# cdz7shld1.net
KiCad netlist of a schematic drawn in EAGLE
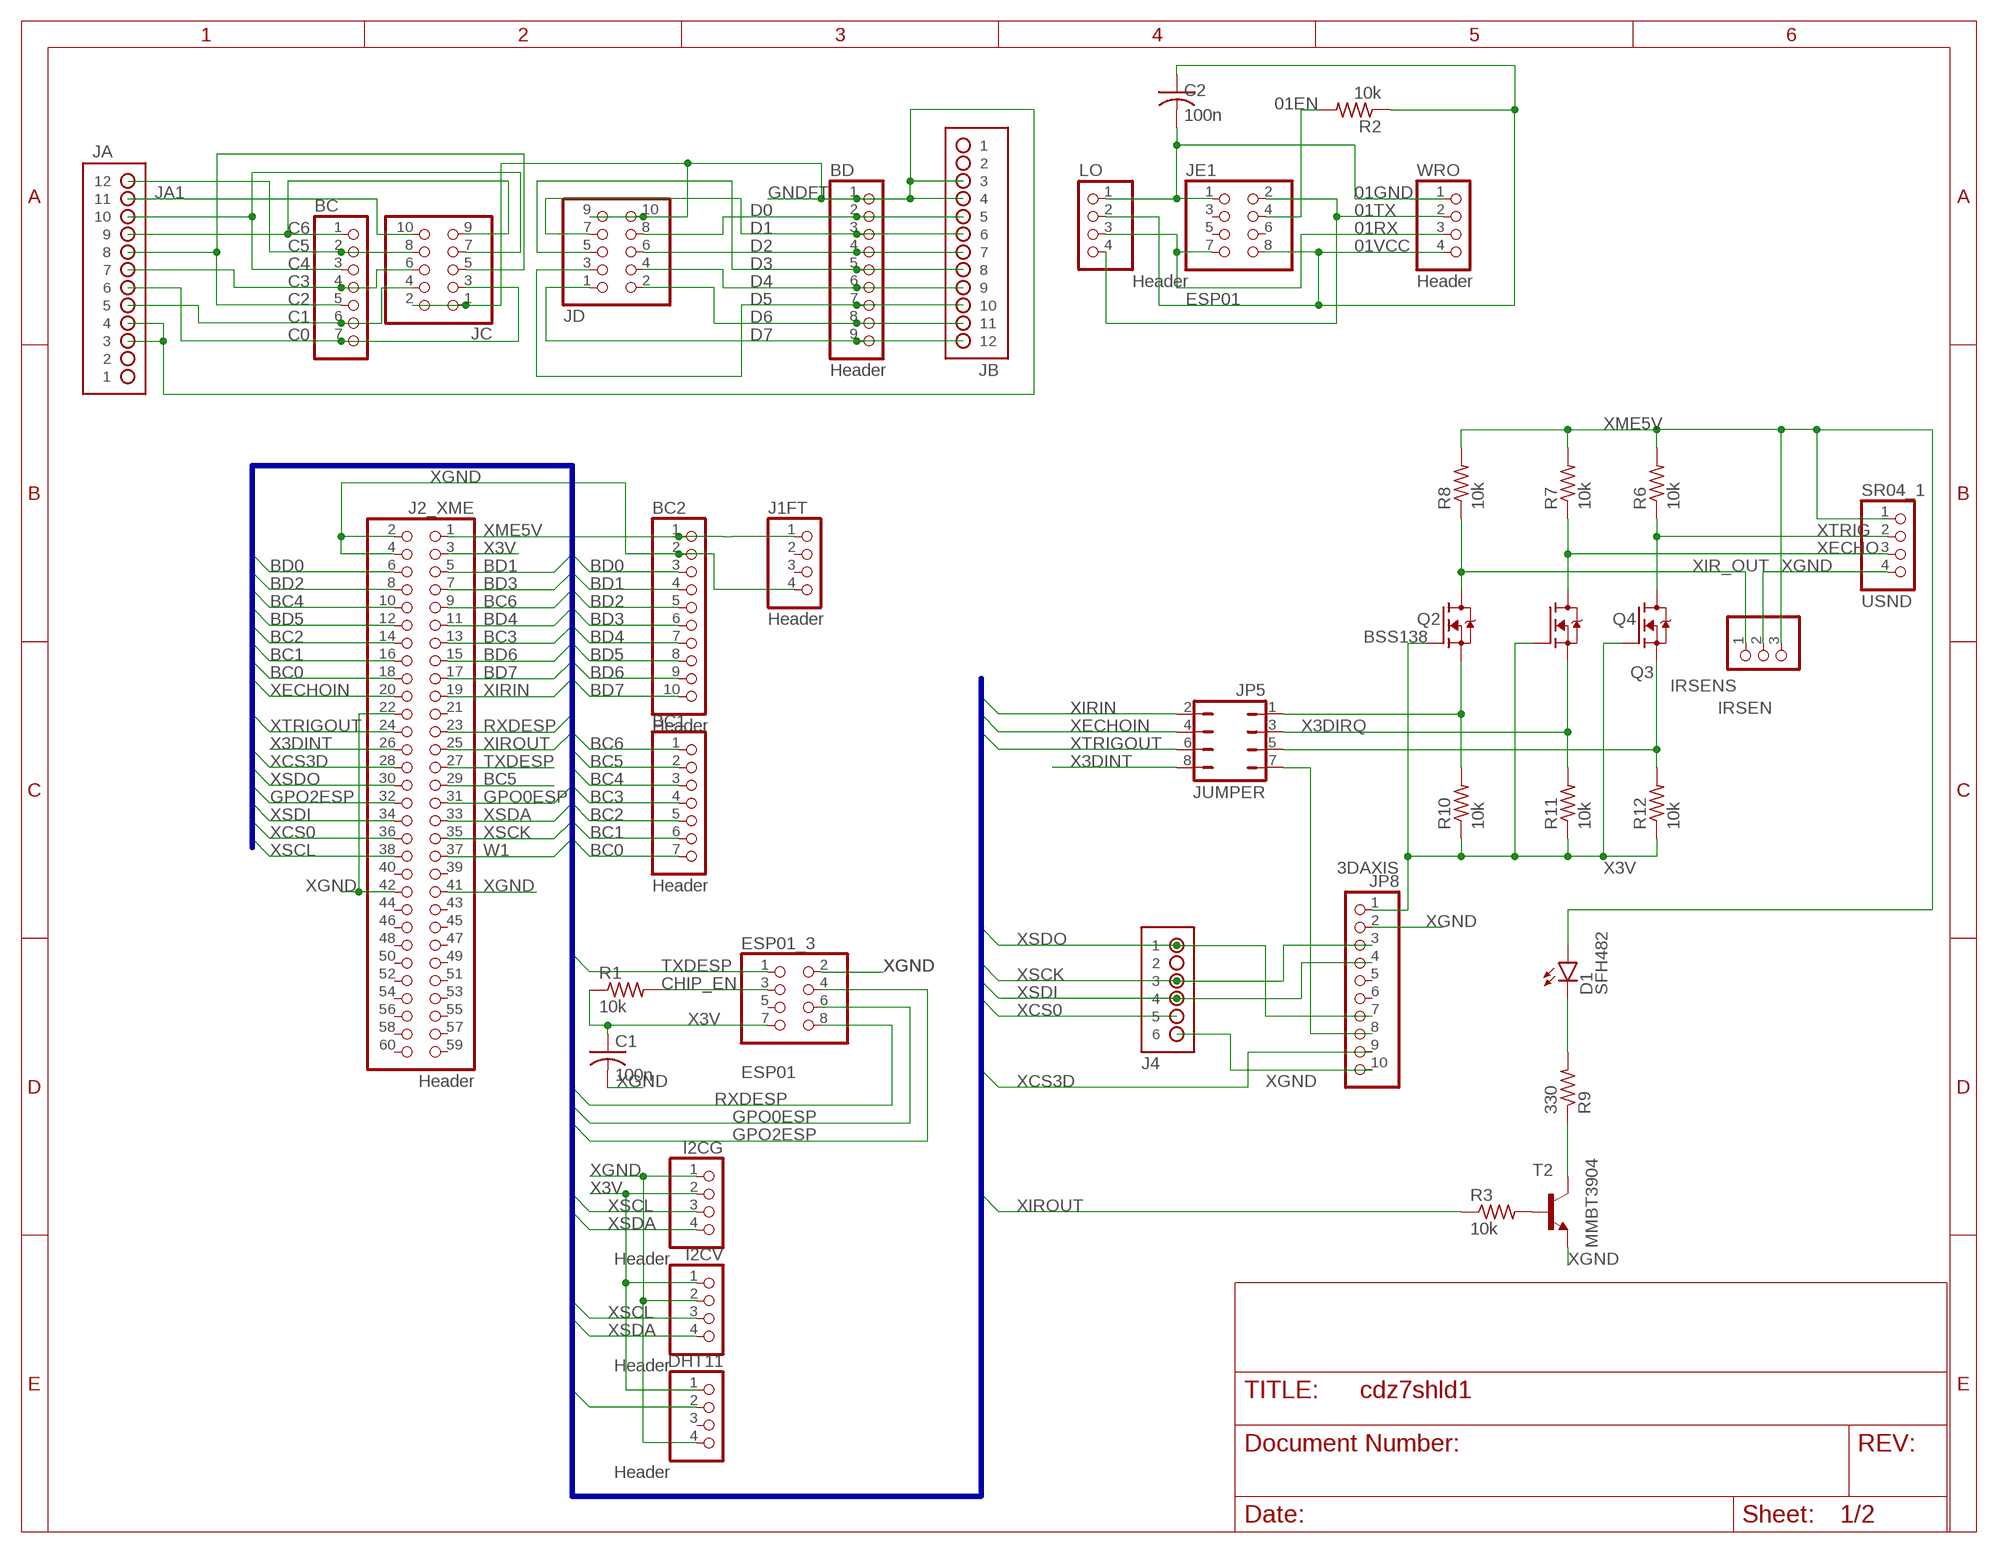
[diagram p0: schematic, sheet 1]
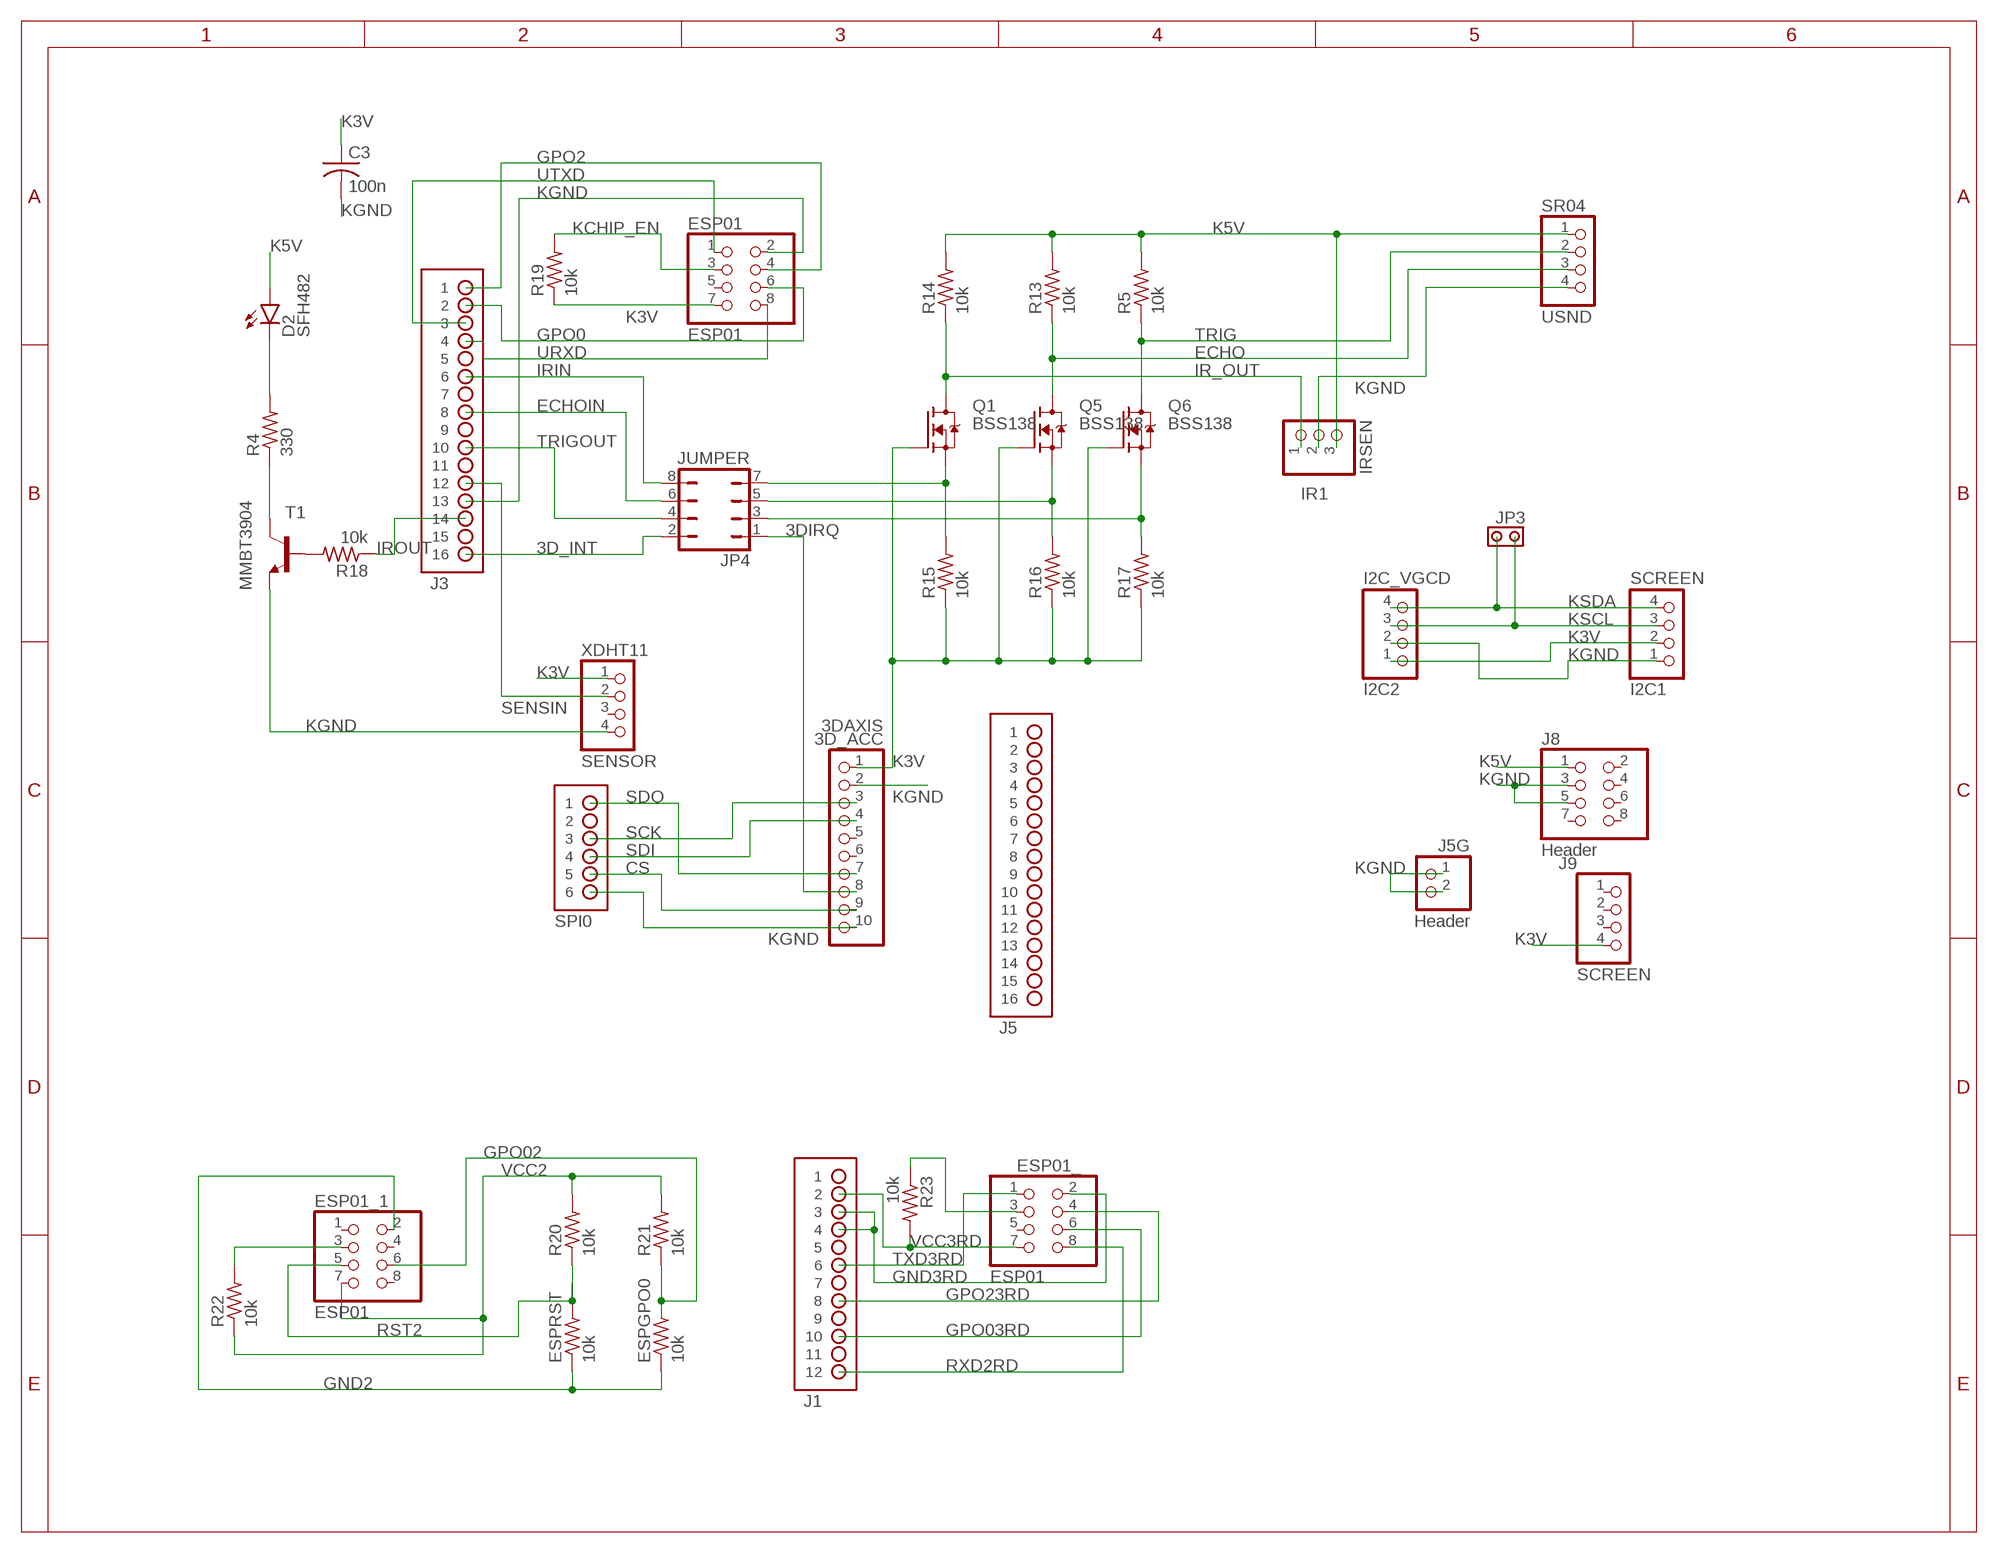
[diagram p1: schematic, sheet 2]

(export (version "E")
  (design (tool "Eeschema 10.0.6"))
  (components
    (comp (ref "3D_ACC")
      (value "3DAXIS")
      (footprint "eagle-import:1X10")
      (libsource (lib "eagle-import") (part "PINHD-1X10"))
    )
    (comp (ref "C3")
      (value "100n")
      (footprint "eagle-import:C0402")
      (libsource (lib "eagle-import") (part "C-USC0402"))
    )
    (comp (ref "D2")
      (value "SFH482")
      (footprint "eagle-import:SFH482")
      (libsource (lib "eagle-import") (part "SFH482"))
    )
    (comp (ref "ESP01")
      (value "ESP01")
      (footprint "eagle-import:2X04")
      (libsource (lib "eagle-import") (part "pinhead_325_PINHD-2X4"))
    )
    (comp (ref "ESP01_")
      (value "ESP01")
      (footprint "eagle-import:2X04")
      (libsource (lib "eagle-import") (part "pinhead_325_PINHD-2X4"))
    )
    (comp (ref "ESP01_1")
      (value "ESP01")
      (footprint "eagle-import:2X04")
      (libsource (lib "eagle-import") (part "pinhead_325_PINHD-2X4"))
    )
    (comp (ref "ESPGPO0")
      (value "10k")
      (footprint "eagle-import:0204_5")
      (libsource (lib "eagle-import") (part "R-US_0204/5"))
    )
    (comp (ref "ESPRST")
      (value "10k")
      (footprint "eagle-import:0204_5")
      (libsource (lib "eagle-import") (part "R-US_0204/5"))
    )
    (comp (ref "I2C1")
      (value "SCREEN")
      (footprint "eagle-import:1X04")
      (libsource (lib "eagle-import") (part "PINHD-1X4"))
    )
    (comp (ref "I2C2")
      (value "I2C_VGCD")
      (footprint "eagle-import:1X04")
      (libsource (lib "eagle-import") (part "PINHD-1X4"))
    )
    (comp (ref "IR1")
      (value "IRSEN")
      (footprint "eagle-import:1X03")
      (libsource (lib "eagle-import") (part "PINHD-1X3"))
    )
    (comp (ref "J1")
      (value "HDR-2X6")
      (footprint "eagle-import:HDR-2X6")
      (libsource (lib "eagle-import") (part "HDR-2X6"))
    )
    (comp (ref "J3")
      (value "HDR-2X8")
      (footprint "eagle-import:HDR-2X8")
      (libsource (lib "eagle-import") (part "HDR-2X8"))
    )
    (comp (ref "J5")
      (value "HDR-2X8")
      (footprint "eagle-import:HDR-2X8")
      (libsource (lib "eagle-import") (part "HDR-2X8"))
    )
    (comp (ref "J5G")
      (value "Header")
      (footprint "eagle-import:1X02")
      (libsource (lib "eagle-import") (part "PINHD-1X2"))
    )
    (comp (ref "J8")
      (value "Header")
      (footprint "eagle-import:2X04")
      (libsource (lib "eagle-import") (part "PINHD-2X4"))
    )
    (comp (ref "J9")
      (value "SCREEN")
      (footprint "eagle-import:1X04")
      (libsource (lib "eagle-import") (part "PINHD-1X4"))
    )
    (comp (ref "JP3")
      (value "JPR-1X2")
      (footprint "eagle-import:JPR-1X2")
      (libsource (lib "eagle-import") (part "JPR-1X2"))
    )
    (comp (ref "JP4")
      (value "JUMPER")
      (footprint "eagle-import:JP4Q")
      (libsource (lib "eagle-import") (part "JP4Q"))
    )
    (comp (ref "Q1")
      (value "BSS138")
      (footprint "eagle-import:SOT23")
      (fields (field (name "MF") "Fairchild"))
      (libsource (lib "eagle-import") (part "BSS138"))
    )
    (comp (ref "Q5")
      (value "BSS138")
      (footprint "eagle-import:SOT23")
      (fields (field (name "MF") "Fairchild"))
      (libsource (lib "eagle-import") (part "BSS138"))
    )
    (comp (ref "Q6")
      (value "BSS138")
      (footprint "eagle-import:SOT23")
      (fields (field (name "MF") "Fairchild"))
      (libsource (lib "eagle-import") (part "BSS138"))
    )
    (comp (ref "R4")
      (value "330")
      (footprint "eagle-import:R0402")
      (libsource (lib "eagle-import") (part "R-US_R0402"))
    )
    (comp (ref "R5")
      (value "10k")
      (footprint "eagle-import:R0402")
      (libsource (lib "eagle-import") (part "R-US_R0402"))
    )
    (comp (ref "R13")
      (value "10k")
      (footprint "eagle-import:R0402")
      (libsource (lib "eagle-import") (part "R-US_R0402"))
    )
    (comp (ref "R14")
      (value "10k")
      (footprint "eagle-import:R0402")
      (libsource (lib "eagle-import") (part "R-US_R0402"))
    )
    (comp (ref "R15")
      (value "10k")
      (footprint "eagle-import:R0402")
      (libsource (lib "eagle-import") (part "R-US_R0402"))
    )
    (comp (ref "R16")
      (value "10k")
      (footprint "eagle-import:R0402")
      (libsource (lib "eagle-import") (part "R-US_R0402"))
    )
    (comp (ref "R17")
      (value "10k")
      (footprint "eagle-import:R0402")
      (libsource (lib "eagle-import") (part "R-US_R0402"))
    )
    (comp (ref "R18")
      (value "10k")
      (footprint "eagle-import:R0402")
      (libsource (lib "eagle-import") (part "R-US_R0402"))
    )
    (comp (ref "R19")
      (value "10k")
      (footprint "eagle-import:R0402")
      (libsource (lib "eagle-import") (part "R-US_R0402"))
    )
    (comp (ref "R20")
      (value "10k")
      (footprint "eagle-import:R0402")
      (libsource (lib "eagle-import") (part "R-US_R0402"))
    )
    (comp (ref "R21")
      (value "10k")
      (footprint "eagle-import:R0402")
      (libsource (lib "eagle-import") (part "R-US_R0402"))
    )
    (comp (ref "R22")
      (value "10k")
      (footprint "eagle-import:R0402")
      (libsource (lib "eagle-import") (part "R-US_R0402"))
    )
    (comp (ref "R23")
      (value "10k")
      (footprint "eagle-import:R0402")
      (libsource (lib "eagle-import") (part "R-US_R0402"))
    )
    (comp (ref "SPI0")
      (value "HDR-2X3")
      (footprint "eagle-import:HDR-2X3")
      (libsource (lib "eagle-import") (part "HDR-2X3"))
    )
    (comp (ref "SR04")
      (value "USND")
      (footprint "eagle-import:1X04")
      (libsource (lib "eagle-import") (part "PINHD-1X4"))
    )
    (comp (ref "T1")
      (value "MMBT3904")
      (footprint "eagle-import:SOT23-BEC")
      (libsource (lib "eagle-import") (part "-NPN-SOT23-BECMMBT3904LT1"))
    )
    (comp (ref "XDHT11")
      (value "SENSOR")
      (footprint "eagle-import:1X04")
      (libsource (lib "eagle-import") (part "PINHD-1X4"))
    )
    (comp (ref "BC")
      (value "Header")
      (footprint "eagle-import:1X07")
      (libsource (lib "eagle-import") (part "PINHD-1X7"))
    )
    (comp (ref "BC1")
      (value "Header")
      (footprint "eagle-import:1X07")
      (libsource (lib "eagle-import") (part "PINHD-1X7"))
    )
    (comp (ref "BC2")
      (value "Header")
      (footprint "eagle-import:1X10")
      (libsource (lib "eagle-import") (part "PINHD-1X10"))
    )
    (comp (ref "BD")
      (value "Header")
      (footprint "eagle-import:1X09")
      (libsource (lib "eagle-import") (part "PINHD-1X9"))
    )
    (comp (ref "C1")
      (value "100n")
      (footprint "eagle-import:C0402")
      (libsource (lib "eagle-import") (part "C-USC0402"))
    )
    (comp (ref "C2")
      (value "100n")
      (footprint "eagle-import:C0402")
      (libsource (lib "eagle-import") (part "C-USC0402"))
    )
    (comp (ref "D1")
      (value "SFH482")
      (footprint "eagle-import:SFH482")
      (libsource (lib "eagle-import") (part "SFH482"))
    )
    (comp (ref "DHT11")
      (value "Header")
      (footprint "eagle-import:1X04")
      (libsource (lib "eagle-import") (part "PINHD-1X4"))
    )
    (comp (ref "ESP01_3")
      (value "ESP01")
      (footprint "eagle-import:2X04")
      (libsource (lib "eagle-import") (part "pinhead_325_PINHD-2X4"))
    )
    (comp (ref "I2CG")
      (value "Header")
      (footprint "eagle-import:1X04")
      (libsource (lib "eagle-import") (part "PINHD-1X4"))
    )
    (comp (ref "I2CV")
      (value "Header")
      (footprint "eagle-import:1X04")
      (libsource (lib "eagle-import") (part "PINHD-1X4"))
    )
    (comp (ref "IRSENS")
      (value "IRSEN")
      (footprint "eagle-import:1X03")
      (libsource (lib "eagle-import") (part "PINHD-1X3"))
    )
    (comp (ref "J1FT")
      (value "Header")
      (footprint "eagle-import:1X04")
      (libsource (lib "eagle-import") (part "PINHD-1X4"))
    )
    (comp (ref "J2_XME")
      (value "Header")
      (footprint "eagle-import:2X30")
      (libsource (lib "eagle-import") (part "PINHD-2X30"))
    )
    (comp (ref "J4")
      (value "HDR-2X3")
      (footprint "eagle-import:HDR-2X3")
      (libsource (lib "eagle-import") (part "HDR-2X3"))
    )
    (comp (ref "JA")
      (value "HDR-2X6")
      (footprint "eagle-import:HDR-2X6")
      (libsource (lib "eagle-import") (part "HDR-2X6"))
    )
    (comp (ref "JB")
      (value "HDR-2X6")
      (footprint "eagle-import:HDR-2X6")
      (libsource (lib "eagle-import") (part "HDR-2X6"))
    )
    (comp (ref "JC")
      (value "Header")
      (footprint "eagle-import:2X05")
      (libsource (lib "eagle-import") (part "PINHD-2X5"))
    )
    (comp (ref "JD")
      (value "Header")
      (footprint "eagle-import:2X05")
      (libsource (lib "eagle-import") (part "PINHD-2X5"))
    )
    (comp (ref "JE1")
      (value "ESP01")
      (footprint "eagle-import:2X04")
      (libsource (lib "eagle-import") (part "pinhead_325_PINHD-2X4"))
    )
    (comp (ref "JP5")
      (value "JUMPER")
      (footprint "eagle-import:JP4Q")
      (libsource (lib "eagle-import") (part "JP4Q"))
    )
    (comp (ref "JP8")
      (value "3DAXIS")
      (footprint "eagle-import:1X10")
      (libsource (lib "eagle-import") (part "PINHD-1X10"))
    )
    (comp (ref "LO")
      (value "Header")
      (footprint "eagle-import:1X04")
      (libsource (lib "eagle-import") (part "PINHD-1X4"))
    )
    (comp (ref "Q2")
      (value "BSS138")
      (footprint "eagle-import:SOT23")
      (fields (field (name "MF") "Fairchild"))
      (libsource (lib "eagle-import") (part "BSS138"))
    )
    (comp (ref "Q3")
      (value "BSS138")
      (footprint "eagle-import:SOT23")
      (fields (field (name "MF") "Fairchild"))
      (libsource (lib "eagle-import") (part "BSS138"))
    )
    (comp (ref "Q4")
      (value "BSS138")
      (footprint "eagle-import:SOT23")
      (fields (field (name "MF") "Fairchild"))
      (libsource (lib "eagle-import") (part "BSS138"))
    )
    (comp (ref "R1")
      (value "10k")
      (footprint "eagle-import:R0402")
      (libsource (lib "eagle-import") (part "R-US_R0402"))
    )
    (comp (ref "R2")
      (value "10k")
      (footprint "eagle-import:R0402")
      (libsource (lib "eagle-import") (part "R-US_R0402"))
    )
    (comp (ref "R3")
      (value "10k")
      (footprint "eagle-import:R0402")
      (libsource (lib "eagle-import") (part "R-US_R0402"))
    )
    (comp (ref "R6")
      (value "10k")
      (footprint "eagle-import:R0402")
      (libsource (lib "eagle-import") (part "R-US_R0402"))
    )
    (comp (ref "R7")
      (value "10k")
      (footprint "eagle-import:R0402")
      (libsource (lib "eagle-import") (part "R-US_R0402"))
    )
    (comp (ref "R8")
      (value "10k")
      (footprint "eagle-import:R0402")
      (libsource (lib "eagle-import") (part "R-US_R0402"))
    )
    (comp (ref "R9")
      (value "330")
      (footprint "eagle-import:R0402")
      (libsource (lib "eagle-import") (part "R-US_R0402"))
    )
    (comp (ref "R10")
      (value "10k")
      (footprint "eagle-import:R0402")
      (libsource (lib "eagle-import") (part "R-US_R0402"))
    )
    (comp (ref "R11")
      (value "10k")
      (footprint "eagle-import:R0402")
      (libsource (lib "eagle-import") (part "R-US_R0402"))
    )
    (comp (ref "R12")
      (value "10k")
      (footprint "eagle-import:R0402")
      (libsource (lib "eagle-import") (part "R-US_R0402"))
    )
    (comp (ref "SR04_1")
      (value "USND")
      (footprint "eagle-import:1X04")
      (libsource (lib "eagle-import") (part "PINHD-1X4"))
    )
    (comp (ref "T2")
      (value "MMBT3904")
      (footprint "eagle-import:SOT23-BEC")
      (libsource (lib "eagle-import") (part "-NPN-SOT23-BECMMBT3904LT1"))
    )
    (comp (ref "WRO")
      (value "Header")
      (footprint "eagle-import:1X04")
      (libsource (lib "eagle-import") (part "PINHD-1X4"))
    )
  )
  (nets
    (net (code "1") (name "01EN") (class "Default")
      (node (ref "JE1") (pin "4") (pinfunction "4_4") (pintype "passive"))
      (node (ref "R2") (pin "2") (pinfunction "2_2") (pintype "passive"))
    )
    (net (code "2") (name "01GND") (class "Default")
      (node (ref "C2") (pin "2") (pinfunction "2_2") (pintype "passive"))
      (node (ref "JE1") (pin "1") (pinfunction "1_1") (pintype "passive"))
      (node (ref "LO") (pin "1") (pinfunction "1_1") (pintype "passive"))
      (node (ref "WRO") (pin "1") (pinfunction "1_1") (pintype "passive"))
    )
    (net (code "3") (name "01RX") (class "Default")
      (node (ref "JE1") (pin "7") (pinfunction "7_7") (pintype "passive"))
      (node (ref "LO") (pin "3") (pinfunction "3_3") (pintype "passive"))
      (node (ref "WRO") (pin "3") (pinfunction "3_3") (pintype "passive"))
    )
    (net (code "4") (name "01TX") (class "Default")
      (node (ref "JE1") (pin "2") (pinfunction "2_2") (pintype "passive"))
      (node (ref "LO") (pin "4") (pinfunction "4_4") (pintype "passive"))
      (node (ref "WRO") (pin "2") (pinfunction "2_2") (pintype "passive"))
    )
    (net (code "5") (name "01VCC") (class "Default")
      (node (ref "C2") (pin "1") (pinfunction "1_1") (pintype "passive"))
      (node (ref "JE1") (pin "8") (pinfunction "8_8") (pintype "passive"))
      (node (ref "LO") (pin "2") (pinfunction "2_2") (pintype "passive"))
      (node (ref "R2") (pin "1") (pinfunction "1_1") (pintype "passive"))
      (node (ref "WRO") (pin "4") (pinfunction "4_4") (pintype "passive"))
    )
    (net (code "6") (name "3DIRQ") (class "Default")
      (node (ref "3D_ACC") (pin "8") (pinfunction "8_8") (pintype "passive"))
      (node (ref "JP4") (pin "1") (pinfunction "1_1") (pintype "passive"))
    )
    (net (code "7") (name "3D_INT") (class "Default")
      (node (ref "J3") (pin "16") (pinfunction "16_16") (pintype "passive"))
      (node (ref "JP4") (pin "2") (pinfunction "2_2") (pintype "passive"))
    )
    (net (code "8") (name "BC0") (class "Default")
      (node (ref "BC1") (pin "7") (pinfunction "7_7") (pintype "passive"))
      (node (ref "J2_XME") (pin "18") (pinfunction "18_18") (pintype "passive"))
    )
    (net (code "9") (name "BC1") (class "Default")
      (node (ref "BC1") (pin "6") (pinfunction "6_6") (pintype "passive"))
      (node (ref "J2_XME") (pin "16") (pinfunction "16_16") (pintype "passive"))
    )
    (net (code "10") (name "BC2") (class "Default")
      (node (ref "BC1") (pin "5") (pinfunction "5_5") (pintype "passive"))
      (node (ref "J2_XME") (pin "14") (pinfunction "14_14") (pintype "passive"))
    )
    (net (code "11") (name "BC3") (class "Default")
      (node (ref "BC1") (pin "4") (pinfunction "4_4") (pintype "passive"))
      (node (ref "J2_XME") (pin "13") (pinfunction "13_13") (pintype "passive"))
    )
    (net (code "12") (name "BC4") (class "Default")
      (node (ref "BC1") (pin "3") (pinfunction "3_3") (pintype "passive"))
      (node (ref "J2_XME") (pin "10") (pinfunction "10_10") (pintype "passive"))
    )
    (net (code "13") (name "BC5") (class "Default")
      (node (ref "BC1") (pin "2") (pinfunction "2_2") (pintype "passive"))
      (node (ref "J2_XME") (pin "29") (pinfunction "29_29") (pintype "passive"))
    )
    (net (code "14") (name "BC6") (class "Default")
      (node (ref "BC1") (pin "1") (pinfunction "1_1") (pintype "passive"))
      (node (ref "J2_XME") (pin "9") (pinfunction "9_9") (pintype "passive"))
    )
    (net (code "15") (name "BD0") (class "Default")
      (node (ref "BC2") (pin "3") (pinfunction "3_3") (pintype "passive"))
      (node (ref "J2_XME") (pin "6") (pinfunction "6_6") (pintype "passive"))
    )
    (net (code "16") (name "BD1") (class "Default")
      (node (ref "BC2") (pin "4") (pinfunction "4_4") (pintype "passive"))
      (node (ref "J2_XME") (pin "5") (pinfunction "5_5") (pintype "passive"))
    )
    (net (code "17") (name "BD2") (class "Default")
      (node (ref "BC2") (pin "5") (pinfunction "5_5") (pintype "passive"))
      (node (ref "J2_XME") (pin "8") (pinfunction "8_8") (pintype "passive"))
    )
    (net (code "18") (name "BD3") (class "Default")
      (node (ref "BC2") (pin "6") (pinfunction "6_6") (pintype "passive"))
      (node (ref "J2_XME") (pin "7") (pinfunction "7_7") (pintype "passive"))
    )
    (net (code "19") (name "BD4") (class "Default")
      (node (ref "BC2") (pin "7") (pinfunction "7_7") (pintype "passive"))
      (node (ref "J2_XME") (pin "11") (pinfunction "11_11") (pintype "passive"))
    )
    (net (code "20") (name "BD5") (class "Default")
      (node (ref "BC2") (pin "8") (pinfunction "8_8") (pintype "passive"))
      (node (ref "J2_XME") (pin "12") (pinfunction "12_12") (pintype "passive"))
    )
    (net (code "21") (name "BD6") (class "Default")
      (node (ref "BC2") (pin "9") (pinfunction "9_9") (pintype "passive"))
      (node (ref "J2_XME") (pin "15") (pinfunction "15_15") (pintype "passive"))
    )
    (net (code "22") (name "BD7") (class "Default")
      (node (ref "BC2") (pin "10") (pinfunction "10_10") (pintype "passive"))
      (node (ref "J2_XME") (pin "17") (pinfunction "17_17") (pintype "passive"))
    )
    (net (code "23") (name "C0") (class "Default")
      (node (ref "BC") (pin "7") (pinfunction "7_7") (pintype "passive"))
      (node (ref "JA") (pin "6") (pinfunction "6_6") (pintype "passive"))
      (node (ref "JC") (pin "3") (pinfunction "3_3") (pintype "passive"))
    )
    (net (code "24") (name "C1") (class "Default")
      (node (ref "BC") (pin "6") (pinfunction "6_6") (pintype "passive"))
      (node (ref "JA") (pin "5") (pinfunction "5_5") (pintype "passive"))
      (node (ref "JC") (pin "4") (pinfunction "4_4") (pintype "passive"))
    )
    (net (code "25") (name "C2") (class "Default")
      (node (ref "BC") (pin "5") (pinfunction "5_5") (pintype "passive"))
      (node (ref "JA") (pin "8") (pinfunction "8_8") (pintype "passive"))
      (node (ref "JC") (pin "5") (pinfunction "5_5") (pintype "passive"))
    )
    (net (code "26") (name "C3") (class "Default")
      (node (ref "BC") (pin "4") (pinfunction "4_4") (pintype "passive"))
      (node (ref "JA") (pin "7") (pinfunction "7_7") (pintype "passive"))
      (node (ref "JC") (pin "6") (pinfunction "6_6") (pintype "passive"))
    )
    (net (code "27") (name "C4") (class "Default")
      (node (ref "BC") (pin "3") (pinfunction "3_3") (pintype "passive"))
      (node (ref "JA") (pin "10") (pinfunction "10_10") (pintype "passive"))
      (node (ref "JC") (pin "7") (pinfunction "7_7") (pintype "passive"))
    )
    (net (code "28") (name "C5") (class "Default")
      (node (ref "BC") (pin "2") (pinfunction "2_2") (pintype "passive"))
      (node (ref "JA") (pin "12") (pinfunction "12_12") (pintype "passive"))
      (node (ref "JC") (pin "8") (pinfunction "8_8") (pintype "passive"))
    )
    (net (code "29") (name "C6") (class "Default")
      (node (ref "BC") (pin "1") (pinfunction "1_1") (pintype "passive"))
      (node (ref "JA") (pin "9") (pinfunction "9_9") (pintype "passive"))
      (node (ref "JC") (pin "9") (pinfunction "9_9") (pintype "passive"))
    )
    (net (code "30") (name "CHIP_EN") (class "Default")
      (node (ref "ESP01_3") (pin "3") (pinfunction "3_3") (pintype "passive"))
      (node (ref "R1") (pin "2") (pinfunction "2_2") (pintype "passive"))
    )
    (net (code "31") (name "CS") (class "Default")
      (node (ref "3D_ACC") (pin "9") (pinfunction "9_9") (pintype "passive"))
      (node (ref "SPI0") (pin "5") (pinfunction "5_5") (pintype "passive"))
    )
    (net (code "32") (name "D0") (class "Default")
      (node (ref "BD") (pin "2") (pinfunction "2_2") (pintype "passive"))
      (node (ref "JB") (pin "5") (pinfunction "5_5") (pintype "passive"))
      (node (ref "JD") (pin "8") (pinfunction "8_8") (pintype "passive"))
    )
    (net (code "33") (name "D1") (class "Default")
      (node (ref "BD") (pin "3") (pinfunction "3_3") (pintype "passive"))
      (node (ref "JB") (pin "6") (pinfunction "6_6") (pintype "passive"))
      (node (ref "JD") (pin "7") (pinfunction "7_7") (pintype "passive"))
    )
    (net (code "34") (name "D2") (class "Default")
      (node (ref "BD") (pin "4") (pinfunction "4_4") (pintype "passive"))
      (node (ref "JB") (pin "7") (pinfunction "7_7") (pintype "passive"))
      (node (ref "JD") (pin "6") (pinfunction "6_6") (pintype "passive"))
    )
    (net (code "35") (name "D3") (class "Default")
      (node (ref "BD") (pin "5") (pinfunction "5_5") (pintype "passive"))
      (node (ref "JB") (pin "8") (pinfunction "8_8") (pintype "passive"))
      (node (ref "JD") (pin "5") (pinfunction "5_5") (pintype "passive"))
    )
    (net (code "36") (name "D4") (class "Default")
      (node (ref "BD") (pin "6") (pinfunction "6_6") (pintype "passive"))
      (node (ref "JB") (pin "9") (pinfunction "9_9") (pintype "passive"))
      (node (ref "JD") (pin "4") (pinfunction "4_4") (pintype "passive"))
    )
    (net (code "37") (name "D5") (class "Default")
      (node (ref "BD") (pin "7") (pinfunction "7_7") (pintype "passive"))
      (node (ref "JB") (pin "10") (pinfunction "10_10") (pintype "passive"))
      (node (ref "JD") (pin "3") (pinfunction "3_3") (pintype "passive"))
    )
    (net (code "38") (name "D6") (class "Default")
      (node (ref "BD") (pin "8") (pinfunction "8_8") (pintype "passive"))
      (node (ref "JB") (pin "11") (pinfunction "11_11") (pintype "passive"))
      (node (ref "JD") (pin "2") (pinfunction "2_2") (pintype "passive"))
    )
    (net (code "39") (name "D7") (class "Default")
      (node (ref "BD") (pin "9") (pinfunction "9_9") (pintype "passive"))
      (node (ref "JB") (pin "12") (pinfunction "12_12") (pintype "passive"))
      (node (ref "JD") (pin "1") (pinfunction "1_1") (pintype "passive"))
    )
    (net (code "40") (name "ECHO") (class "Default")
      (node (ref "Q5") (pin "3") (pinfunction "D_3") (pintype "passive"))
      (node (ref "R13") (pin "1") (pinfunction "1_1") (pintype "passive"))
      (node (ref "SR04") (pin "3") (pinfunction "3_3") (pintype "passive"))
    )
    (net (code "41") (name "ECHOIN") (class "Default")
      (node (ref "J3") (pin "8") (pinfunction "8_8") (pintype "passive"))
      (node (ref "JP4") (pin "6") (pinfunction "6_6") (pintype "passive"))
    )
    (net (code "42") (name "GND2") (class "Default")
      (node (ref "ESP01_1") (pin "2") (pinfunction "2_2") (pintype "passive"))
      (node (ref "ESPGPO0") (pin "1") (pinfunction "1_1") (pintype "passive"))
      (node (ref "ESPRST") (pin "1") (pinfunction "1_1") (pintype "passive"))
    )
    (net (code "43") (name "GND3RD") (class "Default")
      (node (ref "ESP01_") (pin "2") (pinfunction "2_2") (pintype "passive"))
      (node (ref "J1") (pin "3") (pinfunction "3_3") (pintype "passive"))
      (node (ref "J1") (pin "4") (pinfunction "4_4") (pintype "passive"))
    )
    (net (code "44") (name "GNDFT") (class "Default")
      (node (ref "BD") (pin "1") (pinfunction "1_1") (pintype "passive"))
      (node (ref "JA") (pin "3") (pinfunction "3_3") (pintype "passive"))
      (node (ref "JA") (pin "4") (pinfunction "4_4") (pintype "passive"))
      (node (ref "JB") (pin "3") (pinfunction "3_3") (pintype "passive"))
      (node (ref "JB") (pin "4") (pinfunction "4_4") (pintype "passive"))
      (node (ref "JC") (pin "1") (pinfunction "1_1") (pintype "passive"))
      (node (ref "JC") (pin "2") (pinfunction "2_2") (pintype "passive"))
      (node (ref "JD") (pin "10") (pinfunction "10_10") (pintype "passive"))
      (node (ref "JD") (pin "9") (pinfunction "9_9") (pintype "passive"))
    )
    (net (code "45") (name "GPO0") (class "Default")
      (node (ref "ESP01") (pin "6") (pinfunction "6_6") (pintype "passive"))
      (node (ref "J3") (pin "2") (pinfunction "2_2") (pintype "passive"))
    )
    (net (code "46") (name "GPO0ESP") (class "Default")
      (node (ref "ESP01_3") (pin "6") (pinfunction "6_6") (pintype "passive"))
      (node (ref "J2_XME") (pin "31") (pinfunction "31_31") (pintype "passive"))
    )
    (net (code "47") (name "GPO02") (class "Default")
      (node (ref "ESP01_1") (pin "6") (pinfunction "6_6") (pintype "passive"))
      (node (ref "ESPGPO0") (pin "2") (pinfunction "2_2") (pintype "passive"))
      (node (ref "R21") (pin "1") (pinfunction "1_1") (pintype "passive"))
    )
    (net (code "48") (name "GPO2") (class "Default")
      (node (ref "ESP01") (pin "4") (pinfunction "4_4") (pintype "passive"))
      (node (ref "J3") (pin "1") (pinfunction "1_1") (pintype "passive"))
    )
    (net (code "49") (name "GPO2ESP") (class "Default")
      (node (ref "ESP01_3") (pin "4") (pinfunction "4_4") (pintype "passive"))
      (node (ref "J2_XME") (pin "32") (pinfunction "32_32") (pintype "passive"))
    )
    (net (code "50") (name "GPO03RD") (class "Default")
      (node (ref "ESP01_") (pin "6") (pinfunction "6_6") (pintype "passive"))
      (node (ref "J1") (pin "10") (pinfunction "10_10") (pintype "passive"))
    )
    (net (code "51") (name "GPO23RD") (class "Default")
      (node (ref "ESP01_") (pin "4") (pinfunction "4_4") (pintype "passive"))
      (node (ref "J1") (pin "8") (pinfunction "8_8") (pintype "passive"))
    )
    (net (code "52") (name "IRIN") (class "Default")
      (node (ref "J3") (pin "6") (pinfunction "6_6") (pintype "passive"))
      (node (ref "JP4") (pin "8") (pinfunction "8_8") (pintype "passive"))
    )
    (net (code "53") (name "IROUT") (class "Default")
      (node (ref "J3") (pin "14") (pinfunction "14_14") (pintype "passive"))
      (node (ref "R18") (pin "1") (pinfunction "1_1") (pintype "passive"))
    )
    (net (code "54") (name "IR_OUT") (class "Default")
      (node (ref "IR1") (pin "1") (pinfunction "1_1") (pintype "passive"))
      (node (ref "Q1") (pin "3") (pinfunction "D_3") (pintype "passive"))
      (node (ref "R14") (pin "1") (pinfunction "1_1") (pintype "passive"))
    )
    (net (code "55") (name "JA1") (class "Default")
      (node (ref "JA") (pin "11") (pinfunction "11_11") (pintype "passive"))
      (node (ref "JC") (pin "10") (pinfunction "10_10") (pintype "passive"))
    )
    (net (code "56") (name "K3V") (class "Default")
      (node (ref "3D_ACC") (pin "1") (pinfunction "1_1") (pintype "passive"))
      (node (ref "C3") (pin "1") (pinfunction "1_1") (pintype "passive"))
      (node (ref "ESP01") (pin "7") (pinfunction "7_7") (pintype "passive"))
      (node (ref "I2C1") (pin "2") (pinfunction "2_2") (pintype "passive"))
      (node (ref "I2C2") (pin "1") (pinfunction "1_1") (pintype "passive"))
      (node (ref "J9") (pin "4") (pinfunction "4_4") (pintype "passive"))
      (node (ref "Q1") (pin "1") (pinfunction "G_1") (pintype "passive"))
      (node (ref "Q5") (pin "1") (pinfunction "G_1") (pintype "passive"))
      (node (ref "Q6") (pin "1") (pinfunction "G_1") (pintype "passive"))
      (node (ref "R15") (pin "1") (pinfunction "1_1") (pintype "passive"))
      (node (ref "R16") (pin "1") (pinfunction "1_1") (pintype "passive"))
      (node (ref "R17") (pin "1") (pinfunction "1_1") (pintype "passive"))
      (node (ref "R19") (pin "1") (pinfunction "1_1") (pintype "passive"))
      (node (ref "XDHT11") (pin "1") (pinfunction "1_1") (pintype "passive"))
    )
    (net (code "57") (name "K5V") (class "Default")
      (node (ref "D2") (pin "A") (pinfunction "A_A") (pintype "passive"))
      (node (ref "IR1") (pin "3") (pinfunction "3_3") (pintype "passive"))
      (node (ref "J8") (pin "1") (pinfunction "1_1") (pintype "passive"))
      (node (ref "R13") (pin "2") (pinfunction "2_2") (pintype "passive"))
      (node (ref "R14") (pin "2") (pinfunction "2_2") (pintype "passive"))
      (node (ref "R5") (pin "2") (pinfunction "2_2") (pintype "passive"))
      (node (ref "SR04") (pin "1") (pinfunction "1_1") (pintype "passive"))
    )
    (net (code "58") (name "KCHIP_EN") (class "Default")
      (node (ref "ESP01") (pin "3") (pinfunction "3_3") (pintype "passive"))
      (node (ref "R19") (pin "2") (pinfunction "2_2") (pintype "passive"))
    )
    (net (code "59") (name "KGND") (class "Default")
      (node (ref "3D_ACC") (pin "10") (pinfunction "10_10") (pintype "passive"))
      (node (ref "3D_ACC") (pin "2") (pinfunction "2_2") (pintype "passive"))
      (node (ref "C3") (pin "2") (pinfunction "2_2") (pintype "passive"))
      (node (ref "ESP01") (pin "2") (pinfunction "2_2") (pintype "passive"))
      (node (ref "I2C1") (pin "1") (pinfunction "1_1") (pintype "passive"))
      (node (ref "I2C2") (pin "2") (pinfunction "2_2") (pintype "passive"))
      (node (ref "IR1") (pin "2") (pinfunction "2_2") (pintype "passive"))
      (node (ref "J3") (pin "13") (pinfunction "13_13") (pintype "passive"))
      (node (ref "J5G") (pin "1") (pinfunction "1_1") (pintype "passive"))
      (node (ref "J5G") (pin "2") (pinfunction "2_2") (pintype "passive"))
      (node (ref "J8") (pin "3") (pinfunction "3_3") (pintype "passive"))
      (node (ref "J8") (pin "5") (pinfunction "5_5") (pintype "passive"))
      (node (ref "SPI0") (pin "6") (pinfunction "6_6") (pintype "passive"))
      (node (ref "SR04") (pin "4") (pinfunction "4_4") (pintype "passive"))
      (node (ref "T1") (pin "E") (pinfunction "E_E") (pintype "passive"))
      (node (ref "XDHT11") (pin "4") (pinfunction "4_4") (pintype "passive"))
    )
    (net (code "60") (name "KSCL") (class "Default")
      (node (ref "I2C1") (pin "3") (pinfunction "3_3") (pintype "passive"))
      (node (ref "I2C2") (pin "3") (pinfunction "3_3") (pintype "passive"))
      (node (ref "JP3") (pin "2") (pinfunction "2_2") (pintype "passive"))
    )
    (net (code "61") (name "KSDA") (class "Default")
      (node (ref "I2C1") (pin "4") (pinfunction "4_4") (pintype "passive"))
      (node (ref "I2C2") (pin "4") (pinfunction "4_4") (pintype "passive"))
      (node (ref "JP3") (pin "1") (pinfunction "1_1") (pintype "passive"))
    )
    (net (code "62") (name "Net-(D1-C)") (class "Default")
      (node (ref "D1") (pin "K") (pinfunction "C_K") (pintype "passive"))
      (node (ref "R9") (pin "2") (pinfunction "2_2") (pintype "passive"))
    )
    (net (code "63") (name "Net-(D2-C)") (class "Default")
      (node (ref "D2") (pin "K") (pinfunction "C_K") (pintype "passive"))
      (node (ref "R4") (pin "2") (pinfunction "2_2") (pintype "passive"))
    )
    (net (code "64") (name "Net-(ESP01_-Pad3)") (class "Default")
      (node (ref "ESP01_") (pin "3") (pinfunction "3_3") (pintype "passive"))
      (node (ref "R23") (pin "1") (pinfunction "1_1") (pintype "passive"))
    )
    (net (code "65") (name "Net-(ESP01_1-Pad3)") (class "Default")
      (node (ref "ESP01_1") (pin "3") (pinfunction "3_3") (pintype "passive"))
      (node (ref "R22") (pin "2") (pinfunction "2_2") (pintype "passive"))
    )
    (net (code "66") (name "Net-(Q1-S)") (class "Default")
      (node (ref "JP4") (pin "7") (pinfunction "7_7") (pintype "passive"))
      (node (ref "Q1") (pin "2") (pinfunction "S_2") (pintype "passive"))
      (node (ref "R15") (pin "2") (pinfunction "2_2") (pintype "passive"))
    )
    (net (code "67") (name "Net-(Q2-S)") (class "Default")
      (node (ref "JP5") (pin "1") (pinfunction "1_1") (pintype "passive"))
      (node (ref "Q2") (pin "2") (pinfunction "S_2") (pintype "passive"))
      (node (ref "R10") (pin "2") (pinfunction "2_2") (pintype "passive"))
    )
    (net (code "68") (name "Net-(Q3-S)") (class "Default")
      (node (ref "JP5") (pin "3") (pinfunction "3_3") (pintype "passive"))
      (node (ref "Q3") (pin "2") (pinfunction "S_2") (pintype "passive"))
      (node (ref "R11") (pin "2") (pinfunction "2_2") (pintype "passive"))
    )
    (net (code "69") (name "Net-(Q4-S)") (class "Default")
      (node (ref "JP5") (pin "5") (pinfunction "5_5") (pintype "passive"))
      (node (ref "Q4") (pin "2") (pinfunction "S_2") (pintype "passive"))
      (node (ref "R12") (pin "2") (pinfunction "2_2") (pintype "passive"))
    )
    (net (code "70") (name "Net-(Q5-S)") (class "Default")
      (node (ref "JP4") (pin "5") (pinfunction "5_5") (pintype "passive"))
      (node (ref "Q5") (pin "2") (pinfunction "S_2") (pintype "passive"))
      (node (ref "R16") (pin "2") (pinfunction "2_2") (pintype "passive"))
    )
    (net (code "71") (name "Net-(Q6-S)") (class "Default")
      (node (ref "JP4") (pin "3") (pinfunction "3_3") (pintype "passive"))
      (node (ref "Q6") (pin "2") (pinfunction "S_2") (pintype "passive"))
      (node (ref "R17") (pin "2") (pinfunction "2_2") (pintype "passive"))
    )
    (net (code "72") (name "Net-(R3-Pad2)") (class "Default")
      (node (ref "R3") (pin "2") (pinfunction "2_2") (pintype "passive"))
      (node (ref "T2") (pin "B") (pinfunction "B_B") (pintype "passive"))
    )
    (net (code "73") (name "Net-(R4-Pad1)") (class "Default")
      (node (ref "R4") (pin "1") (pinfunction "1_1") (pintype "passive"))
      (node (ref "T1") (pin "C") (pinfunction "C_C") (pintype "passive"))
    )
    (net (code "74") (name "Net-(R9-Pad1)") (class "Default")
      (node (ref "R9") (pin "1") (pinfunction "1_1") (pintype "passive"))
      (node (ref "T2") (pin "C") (pinfunction "C_C") (pintype "passive"))
    )
    (net (code "75") (name "Net-(R18-Pad2)") (class "Default")
      (node (ref "R18") (pin "2") (pinfunction "2_2") (pintype "passive"))
      (node (ref "T1") (pin "B") (pinfunction "B_B") (pintype "passive"))
    )
    (net (code "76") (name "RST2") (class "Default")
      (node (ref "ESP01_1") (pin "5") (pinfunction "5_5") (pintype "passive"))
      (node (ref "ESPRST") (pin "2") (pinfunction "2_2") (pintype "passive"))
      (node (ref "R20") (pin "1") (pinfunction "1_1") (pintype "passive"))
    )
    (net (code "77") (name "RXD2RD") (class "Default")
      (node (ref "ESP01_") (pin "8") (pinfunction "8_8") (pintype "passive"))
      (node (ref "J1") (pin "12") (pinfunction "12_12") (pintype "passive"))
    )
    (net (code "78") (name "RXDESP") (class "Default")
      (node (ref "ESP01_3") (pin "8") (pinfunction "8_8") (pintype "passive"))
      (node (ref "J2_XME") (pin "23") (pinfunction "23_23") (pintype "passive"))
    )
    (net (code "79") (name "SCK") (class "Default")
      (node (ref "3D_ACC") (pin "3") (pinfunction "3_3") (pintype "passive"))
      (node (ref "SPI0") (pin "3") (pinfunction "3_3") (pintype "passive"))
    )
    (net (code "80") (name "SDI") (class "Default")
      (node (ref "3D_ACC") (pin "4") (pinfunction "4_4") (pintype "passive"))
      (node (ref "SPI0") (pin "4") (pinfunction "4_4") (pintype "passive"))
    )
    (net (code "81") (name "SDO") (class "Default")
      (node (ref "3D_ACC") (pin "7") (pinfunction "7_7") (pintype "passive"))
      (node (ref "SPI0") (pin "1") (pinfunction "1_1") (pintype "passive"))
    )
    (net (code "82") (name "SENSIN") (class "Default")
      (node (ref "J3") (pin "12") (pinfunction "12_12") (pintype "passive"))
      (node (ref "XDHT11") (pin "2") (pinfunction "2_2") (pintype "passive"))
    )
    (net (code "83") (name "TRIG") (class "Default")
      (node (ref "Q6") (pin "3") (pinfunction "D_3") (pintype "passive"))
      (node (ref "R5") (pin "1") (pinfunction "1_1") (pintype "passive"))
      (node (ref "SR04") (pin "2") (pinfunction "2_2") (pintype "passive"))
    )
    (net (code "84") (name "TRIGOUT") (class "Default")
      (node (ref "J3") (pin "10") (pinfunction "10_10") (pintype "passive"))
      (node (ref "JP4") (pin "4") (pinfunction "4_4") (pintype "passive"))
    )
    (net (code "85") (name "TXD3RD") (class "Default")
      (node (ref "ESP01_") (pin "1") (pinfunction "1_1") (pintype "passive"))
      (node (ref "J1") (pin "6") (pinfunction "6_6") (pintype "passive"))
    )
    (net (code "86") (name "TXDESP") (class "Default")
      (node (ref "ESP01_3") (pin "1") (pinfunction "1_1") (pintype "passive"))
      (node (ref "J2_XME") (pin "27") (pinfunction "27_27") (pintype "passive"))
    )
    (net (code "87") (name "URXD") (class "Default")
      (node (ref "ESP01") (pin "8") (pinfunction "8_8") (pintype "passive"))
      (node (ref "J3") (pin "4") (pinfunction "4_4") (pintype "passive"))
    )
    (net (code "88") (name "UTXD") (class "Default")
      (node (ref "ESP01") (pin "1") (pinfunction "1_1") (pintype "passive"))
      (node (ref "J3") (pin "3") (pinfunction "3_3") (pintype "passive"))
    )
    (net (code "89") (name "VCC2") (class "Default")
      (node (ref "ESP01_1") (pin "7") (pinfunction "7_7") (pintype "passive"))
      (node (ref "R20") (pin "2") (pinfunction "2_2") (pintype "passive"))
      (node (ref "R21") (pin "2") (pinfunction "2_2") (pintype "passive"))
      (node (ref "R22") (pin "1") (pinfunction "1_1") (pintype "passive"))
    )
    (net (code "90") (name "VCC3RD") (class "Default")
      (node (ref "ESP01_") (pin "7") (pinfunction "7_7") (pintype "passive"))
      (node (ref "J1") (pin "2") (pinfunction "2_2") (pintype "passive"))
      (node (ref "R23") (pin "2") (pinfunction "2_2") (pintype "passive"))
    )
    (net (code "91") (name "W1") (class "Default")
      (node (ref "DHT11") (pin "2") (pinfunction "2_2") (pintype "passive"))
      (node (ref "J2_XME") (pin "37") (pinfunction "37_37") (pintype "passive"))
    )
    (net (code "92") (name "X3DINT") (class "Default")
      (node (ref "J2_XME") (pin "26") (pinfunction "26_26") (pintype "passive"))
      (node (ref "JP5") (pin "8") (pinfunction "8_8") (pintype "passive"))
    )
    (net (code "93") (name "X3DIRQ") (class "Default")
      (node (ref "JP5") (pin "7") (pinfunction "7_7") (pintype "passive"))
      (node (ref "JP8") (pin "8") (pinfunction "8_8") (pintype "passive"))
    )
    (net (code "94") (name "X3V") (class "Default")
      (node (ref "C1") (pin "1") (pinfunction "1_1") (pintype "passive"))
      (node (ref "DHT11") (pin "1") (pinfunction "1_1") (pintype "passive"))
      (node (ref "ESP01_3") (pin "7") (pinfunction "7_7") (pintype "passive"))
      (node (ref "I2CG") (pin "2") (pinfunction "2_2") (pintype "passive"))
      (node (ref "I2CV") (pin "1") (pinfunction "1_1") (pintype "passive"))
      (node (ref "J2_XME") (pin "3") (pinfunction "3_3") (pintype "passive"))
      (node (ref "JP8") (pin "1") (pinfunction "1_1") (pintype "passive"))
      (node (ref "Q2") (pin "1") (pinfunction "G_1") (pintype "passive"))
      (node (ref "Q3") (pin "1") (pinfunction "G_1") (pintype "passive"))
      (node (ref "Q4") (pin "1") (pinfunction "G_1") (pintype "passive"))
      (node (ref "R1") (pin "1") (pinfunction "1_1") (pintype "passive"))
      (node (ref "R10") (pin "1") (pinfunction "1_1") (pintype "passive"))
      (node (ref "R11") (pin "1") (pinfunction "1_1") (pintype "passive"))
      (node (ref "R12") (pin "1") (pinfunction "1_1") (pintype "passive"))
    )
    (net (code "95") (name "XCS0") (class "Default")
      (node (ref "J2_XME") (pin "36") (pinfunction "36_36") (pintype "passive"))
      (node (ref "J4") (pin "5") (pinfunction "5_5") (pintype "passive"))
    )
    (net (code "96") (name "XCS3D") (class "Default")
      (node (ref "J2_XME") (pin "28") (pinfunction "28_28") (pintype "passive"))
      (node (ref "JP8") (pin "9") (pinfunction "9_9") (pintype "passive"))
    )
    (net (code "97") (name "XECHO") (class "Default")
      (node (ref "Q3") (pin "3") (pinfunction "D_3") (pintype "passive"))
      (node (ref "R7") (pin "1") (pinfunction "1_1") (pintype "passive"))
      (node (ref "SR04_1") (pin "3") (pinfunction "3_3") (pintype "passive"))
    )
    (net (code "98") (name "XECHOIN") (class "Default")
      (node (ref "J2_XME") (pin "20") (pinfunction "20_20") (pintype "passive"))
      (node (ref "JP5") (pin "4") (pinfunction "4_4") (pintype "passive"))
    )
    (net (code "99") (name "XGND") (class "Default")
      (node (ref "BC2") (pin "2") (pinfunction "2_2") (pintype "passive"))
      (node (ref "C1") (pin "2") (pinfunction "2_2") (pintype "passive"))
      (node (ref "DHT11") (pin "4") (pinfunction "4_4") (pintype "passive"))
      (node (ref "ESP01_3") (pin "2") (pinfunction "2_2") (pintype "passive"))
      (node (ref "I2CG") (pin "1") (pinfunction "1_1") (pintype "passive"))
      (node (ref "I2CV") (pin "2") (pinfunction "2_2") (pintype "passive"))
      (node (ref "IRSENS") (pin "2") (pinfunction "2_2") (pintype "passive"))
      (node (ref "J1FT") (pin "4") (pinfunction "4_4") (pintype "passive"))
      (node (ref "J2_XME") (pin "2") (pinfunction "2_2") (pintype "passive"))
      (node (ref "J2_XME") (pin "22") (pinfunction "22_22") (pintype "passive"))
      (node (ref "J2_XME") (pin "4") (pinfunction "4_4") (pintype "passive"))
      (node (ref "J2_XME") (pin "41") (pinfunction "41_41") (pintype "passive"))
      (node (ref "J2_XME") (pin "42") (pinfunction "42_42") (pintype "passive"))
      (node (ref "J4") (pin "6") (pinfunction "6_6") (pintype "passive"))
      (node (ref "JP8") (pin "10") (pinfunction "10_10") (pintype "passive"))
      (node (ref "JP8") (pin "2") (pinfunction "2_2") (pintype "passive"))
      (node (ref "SR04_1") (pin "4") (pinfunction "4_4") (pintype "passive"))
      (node (ref "T2") (pin "E") (pinfunction "E_E") (pintype "passive"))
    )
    (net (code "100") (name "XIRIN") (class "Default")
      (node (ref "J2_XME") (pin "19") (pinfunction "19_19") (pintype "passive"))
      (node (ref "JP5") (pin "2") (pinfunction "2_2") (pintype "passive"))
    )
    (net (code "101") (name "XIROUT") (class "Default")
      (node (ref "J2_XME") (pin "25") (pinfunction "25_25") (pintype "passive"))
      (node (ref "R3") (pin "1") (pinfunction "1_1") (pintype "passive"))
    )
    (net (code "102") (name "XIR_OUT") (class "Default")
      (node (ref "IRSENS") (pin "1") (pinfunction "1_1") (pintype "passive"))
      (node (ref "Q2") (pin "3") (pinfunction "D_3") (pintype "passive"))
      (node (ref "R8") (pin "1") (pinfunction "1_1") (pintype "passive"))
    )
    (net (code "103") (name "XME5V") (class "Default")
      (node (ref "BC2") (pin "1") (pinfunction "1_1") (pintype "passive"))
      (node (ref "D1") (pin "A") (pinfunction "A_A") (pintype "passive"))
      (node (ref "IRSENS") (pin "3") (pinfunction "3_3") (pintype "passive"))
      (node (ref "J1FT") (pin "1") (pinfunction "1_1") (pintype "passive"))
      (node (ref "J2_XME") (pin "1") (pinfunction "1_1") (pintype "passive"))
      (node (ref "R6") (pin "2") (pinfunction "2_2") (pintype "passive"))
      (node (ref "R7") (pin "2") (pinfunction "2_2") (pintype "passive"))
      (node (ref "R8") (pin "2") (pinfunction "2_2") (pintype "passive"))
      (node (ref "SR04_1") (pin "1") (pinfunction "1_1") (pintype "passive"))
    )
    (net (code "104") (name "XSCK") (class "Default")
      (node (ref "J2_XME") (pin "35") (pinfunction "35_35") (pintype "passive"))
      (node (ref "J4") (pin "3") (pinfunction "3_3") (pintype "passive"))
      (node (ref "JP8") (pin "3") (pinfunction "3_3") (pintype "passive"))
    )
    (net (code "105") (name "XSCL") (class "Default")
      (node (ref "I2CG") (pin "3") (pinfunction "3_3") (pintype "passive"))
      (node (ref "I2CV") (pin "3") (pinfunction "3_3") (pintype "passive"))
      (node (ref "J2_XME") (pin "38") (pinfunction "38_38") (pintype "passive"))
    )
    (net (code "106") (name "XSDA") (class "Default")
      (node (ref "I2CG") (pin "4") (pinfunction "4_4") (pintype "passive"))
      (node (ref "I2CV") (pin "4") (pinfunction "4_4") (pintype "passive"))
      (node (ref "J2_XME") (pin "33") (pinfunction "33_33") (pintype "passive"))
    )
    (net (code "107") (name "XSDI") (class "Default")
      (node (ref "J2_XME") (pin "34") (pinfunction "34_34") (pintype "passive"))
      (node (ref "J4") (pin "4") (pinfunction "4_4") (pintype "passive"))
      (node (ref "JP8") (pin "4") (pinfunction "4_4") (pintype "passive"))
    )
    (net (code "108") (name "XSDO") (class "Default")
      (node (ref "J2_XME") (pin "30") (pinfunction "30_30") (pintype "passive"))
      (node (ref "J4") (pin "1") (pinfunction "1_1") (pintype "passive"))
      (node (ref "JP8") (pin "7") (pinfunction "7_7") (pintype "passive"))
    )
    (net (code "109") (name "XTRIG") (class "Default")
      (node (ref "Q4") (pin "3") (pinfunction "D_3") (pintype "passive"))
      (node (ref "R6") (pin "1") (pinfunction "1_1") (pintype "passive"))
      (node (ref "SR04_1") (pin "2") (pinfunction "2_2") (pintype "passive"))
    )
    (net (code "110") (name "XTRIGOUT") (class "Default")
      (node (ref "J2_XME") (pin "24") (pinfunction "24_24") (pintype "passive"))
      (node (ref "JP5") (pin "6") (pinfunction "6_6") (pintype "passive"))
    )
    (net (code "111") (name "unconnected-(3D_ACC-Pad5)") (class "Default")
      (node (ref "3D_ACC") (pin "5") (pinfunction "5_5") (pintype "passive"))
    )
    (net (code "112") (name "unconnected-(3D_ACC-Pad6)") (class "Default")
      (node (ref "3D_ACC") (pin "6") (pinfunction "6_6") (pintype "passive"))
    )
    (net (code "113") (name "unconnected-(DHT11-Pad3)") (class "Default")
      (node (ref "DHT11") (pin "3") (pinfunction "3_3") (pintype "passive"))
    )
    (net (code "114") (name "unconnected-(ESP01-Pad5)") (class "Default")
      (node (ref "ESP01") (pin "5") (pinfunction "5_5") (pintype "passive"))
    )
    (net (code "115") (name "unconnected-(ESP01_-Pad5)") (class "Default")
      (node (ref "ESP01_") (pin "5") (pinfunction "5_5") (pintype "passive"))
    )
    (net (code "116") (name "unconnected-(ESP01_1-Pad1)") (class "Default")
      (node (ref "ESP01_1") (pin "1") (pinfunction "1_1") (pintype "passive"))
    )
    (net (code "117") (name "unconnected-(ESP01_1-Pad4)") (class "Default")
      (node (ref "ESP01_1") (pin "4") (pinfunction "4_4") (pintype "passive"))
    )
    (net (code "118") (name "unconnected-(ESP01_1-Pad8)") (class "Default")
      (node (ref "ESP01_1") (pin "8") (pinfunction "8_8") (pintype "passive"))
    )
    (net (code "119") (name "unconnected-(ESP01_3-Pad5)") (class "Default")
      (node (ref "ESP01_3") (pin "5") (pinfunction "5_5") (pintype "passive"))
    )
    (net (code "120") (name "unconnected-(J1-Pad1)") (class "Default")
      (node (ref "J1") (pin "1") (pinfunction "1_1") (pintype "passive"))
    )
    (net (code "121") (name "unconnected-(J1-Pad5)") (class "Default")
      (node (ref "J1") (pin "5") (pinfunction "5_5") (pintype "passive"))
    )
    (net (code "122") (name "unconnected-(J1-Pad7)") (class "Default")
      (node (ref "J1") (pin "7") (pinfunction "7_7") (pintype "passive"))
    )
    (net (code "123") (name "unconnected-(J1-Pad9)") (class "Default")
      (node (ref "J1") (pin "9") (pinfunction "9_9") (pintype "passive"))
    )
    (net (code "124") (name "unconnected-(J1-Pad11)") (class "Default")
      (node (ref "J1") (pin "11") (pinfunction "11_11") (pintype "passive"))
    )
    (net (code "125") (name "unconnected-(J1FT-Pad2)") (class "Default")
      (node (ref "J1FT") (pin "2") (pinfunction "2_2") (pintype "passive"))
    )
    (net (code "126") (name "unconnected-(J1FT-Pad3)") (class "Default")
      (node (ref "J1FT") (pin "3") (pinfunction "3_3") (pintype "passive"))
    )
    (net (code "127") (name "unconnected-(J2_XME-Pad21)") (class "Default")
      (node (ref "J2_XME") (pin "21") (pinfunction "21_21") (pintype "passive"))
    )
    (net (code "128") (name "unconnected-(J2_XME-Pad39)") (class "Default")
      (node (ref "J2_XME") (pin "39") (pinfunction "39_39") (pintype "passive"))
    )
    (net (code "129") (name "unconnected-(J2_XME-Pad40)") (class "Default")
      (node (ref "J2_XME") (pin "40") (pinfunction "40_40") (pintype "passive"))
    )
    (net (code "130") (name "unconnected-(J2_XME-Pad43)") (class "Default")
      (node (ref "J2_XME") (pin "43") (pinfunction "43_43") (pintype "passive"))
    )
    (net (code "131") (name "unconnected-(J2_XME-Pad44)") (class "Default")
      (node (ref "J2_XME") (pin "44") (pinfunction "44_44") (pintype "passive"))
    )
    (net (code "132") (name "unconnected-(J2_XME-Pad45)") (class "Default")
      (node (ref "J2_XME") (pin "45") (pinfunction "45_45") (pintype "passive"))
    )
    (net (code "133") (name "unconnected-(J2_XME-Pad46)") (class "Default")
      (node (ref "J2_XME") (pin "46") (pinfunction "46_46") (pintype "passive"))
    )
    (net (code "134") (name "unconnected-(J2_XME-Pad47)") (class "Default")
      (node (ref "J2_XME") (pin "47") (pinfunction "47_47") (pintype "passive"))
    )
    (net (code "135") (name "unconnected-(J2_XME-Pad48)") (class "Default")
      (node (ref "J2_XME") (pin "48") (pinfunction "48_48") (pintype "passive"))
    )
    (net (code "136") (name "unconnected-(J2_XME-Pad49)") (class "Default")
      (node (ref "J2_XME") (pin "49") (pinfunction "49_49") (pintype "passive"))
    )
    (net (code "137") (name "unconnected-(J2_XME-Pad50)") (class "Default")
      (node (ref "J2_XME") (pin "50") (pinfunction "50_50") (pintype "passive"))
    )
    (net (code "138") (name "unconnected-(J2_XME-Pad51)") (class "Default")
      (node (ref "J2_XME") (pin "51") (pinfunction "51_51") (pintype "passive"))
    )
    (net (code "139") (name "unconnected-(J2_XME-Pad52)") (class "Default")
      (node (ref "J2_XME") (pin "52") (pinfunction "52_52") (pintype "passive"))
    )
    (net (code "140") (name "unconnected-(J2_XME-Pad53)") (class "Default")
      (node (ref "J2_XME") (pin "53") (pinfunction "53_53") (pintype "passive"))
    )
    (net (code "141") (name "unconnected-(J2_XME-Pad54)") (class "Default")
      (node (ref "J2_XME") (pin "54") (pinfunction "54_54") (pintype "passive"))
    )
    (net (code "142") (name "unconnected-(J2_XME-Pad55)") (class "Default")
      (node (ref "J2_XME") (pin "55") (pinfunction "55_55") (pintype "passive"))
    )
    (net (code "143") (name "unconnected-(J2_XME-Pad56)") (class "Default")
      (node (ref "J2_XME") (pin "56") (pinfunction "56_56") (pintype "passive"))
    )
    (net (code "144") (name "unconnected-(J2_XME-Pad57)") (class "Default")
      (node (ref "J2_XME") (pin "57") (pinfunction "57_57") (pintype "passive"))
    )
    (net (code "145") (name "unconnected-(J2_XME-Pad58)") (class "Default")
      (node (ref "J2_XME") (pin "58") (pinfunction "58_58") (pintype "passive"))
    )
    (net (code "146") (name "unconnected-(J2_XME-Pad59)") (class "Default")
      (node (ref "J2_XME") (pin "59") (pinfunction "59_59") (pintype "passive"))
    )
    (net (code "147") (name "unconnected-(J2_XME-Pad60)") (class "Default")
      (node (ref "J2_XME") (pin "60") (pinfunction "60_60") (pintype "passive"))
    )
    (net (code "148") (name "unconnected-(J3-Pad5)") (class "Default")
      (node (ref "J3") (pin "5") (pinfunction "5_5") (pintype "passive"))
    )
    (net (code "149") (name "unconnected-(J3-Pad7)") (class "Default")
      (node (ref "J3") (pin "7") (pinfunction "7_7") (pintype "passive"))
    )
    (net (code "150") (name "unconnected-(J3-Pad9)") (class "Default")
      (node (ref "J3") (pin "9") (pinfunction "9_9") (pintype "passive"))
    )
    (net (code "151") (name "unconnected-(J3-Pad11)") (class "Default")
      (node (ref "J3") (pin "11") (pinfunction "11_11") (pintype "passive"))
    )
    (net (code "152") (name "unconnected-(J3-Pad15)") (class "Default")
      (node (ref "J3") (pin "15") (pinfunction "15_15") (pintype "passive"))
    )
    (net (code "153") (name "unconnected-(J4-Pad2)") (class "Default")
      (node (ref "J4") (pin "2") (pinfunction "2_2") (pintype "passive"))
    )
    (net (code "154") (name "unconnected-(J5-Pad1)") (class "Default")
      (node (ref "J5") (pin "1") (pinfunction "1_1") (pintype "passive"))
    )
    (net (code "155") (name "unconnected-(J5-Pad2)") (class "Default")
      (node (ref "J5") (pin "2") (pinfunction "2_2") (pintype "passive"))
    )
    (net (code "156") (name "unconnected-(J5-Pad3)") (class "Default")
      (node (ref "J5") (pin "3") (pinfunction "3_3") (pintype "passive"))
    )
    (net (code "157") (name "unconnected-(J5-Pad4)") (class "Default")
      (node (ref "J5") (pin "4") (pinfunction "4_4") (pintype "passive"))
    )
    (net (code "158") (name "unconnected-(J5-Pad5)") (class "Default")
      (node (ref "J5") (pin "5") (pinfunction "5_5") (pintype "passive"))
    )
    (net (code "159") (name "unconnected-(J5-Pad6)") (class "Default")
      (node (ref "J5") (pin "6") (pinfunction "6_6") (pintype "passive"))
    )
    (net (code "160") (name "unconnected-(J5-Pad7)") (class "Default")
      (node (ref "J5") (pin "7") (pinfunction "7_7") (pintype "passive"))
    )
    (net (code "161") (name "unconnected-(J5-Pad8)") (class "Default")
      (node (ref "J5") (pin "8") (pinfunction "8_8") (pintype "passive"))
    )
    (net (code "162") (name "unconnected-(J5-Pad9)") (class "Default")
      (node (ref "J5") (pin "9") (pinfunction "9_9") (pintype "passive"))
    )
    (net (code "163") (name "unconnected-(J5-Pad10)") (class "Default")
      (node (ref "J5") (pin "10") (pinfunction "10_10") (pintype "passive"))
    )
    (net (code "164") (name "unconnected-(J5-Pad11)") (class "Default")
      (node (ref "J5") (pin "11") (pinfunction "11_11") (pintype "passive"))
    )
    (net (code "165") (name "unconnected-(J5-Pad12)") (class "Default")
      (node (ref "J5") (pin "12") (pinfunction "12_12") (pintype "passive"))
    )
    (net (code "166") (name "unconnected-(J5-Pad13)") (class "Default")
      (node (ref "J5") (pin "13") (pinfunction "13_13") (pintype "passive"))
    )
    (net (code "167") (name "unconnected-(J5-Pad14)") (class "Default")
      (node (ref "J5") (pin "14") (pinfunction "14_14") (pintype "passive"))
    )
    (net (code "168") (name "unconnected-(J5-Pad15)") (class "Default")
      (node (ref "J5") (pin "15") (pinfunction "15_15") (pintype "passive"))
    )
    (net (code "169") (name "unconnected-(J5-Pad16)") (class "Default")
      (node (ref "J5") (pin "16") (pinfunction "16_16") (pintype "passive"))
    )
    (net (code "170") (name "unconnected-(J8-Pad2)") (class "Default")
      (node (ref "J8") (pin "2") (pinfunction "2_2") (pintype "passive"))
    )
    (net (code "171") (name "unconnected-(J8-Pad4)") (class "Default")
      (node (ref "J8") (pin "4") (pinfunction "4_4") (pintype "passive"))
    )
    (net (code "172") (name "unconnected-(J8-Pad6)") (class "Default")
      (node (ref "J8") (pin "6") (pinfunction "6_6") (pintype "passive"))
    )
    (net (code "173") (name "unconnected-(J8-Pad7)") (class "Default")
      (node (ref "J8") (pin "7") (pinfunction "7_7") (pintype "passive"))
    )
    (net (code "174") (name "unconnected-(J8-Pad8)") (class "Default")
      (node (ref "J8") (pin "8") (pinfunction "8_8") (pintype "passive"))
    )
    (net (code "175") (name "unconnected-(J9-Pad1)") (class "Default")
      (node (ref "J9") (pin "1") (pinfunction "1_1") (pintype "passive"))
    )
    (net (code "176") (name "unconnected-(J9-Pad2)") (class "Default")
      (node (ref "J9") (pin "2") (pinfunction "2_2") (pintype "passive"))
    )
    (net (code "177") (name "unconnected-(J9-Pad3)") (class "Default")
      (node (ref "J9") (pin "3") (pinfunction "3_3") (pintype "passive"))
    )
    (net (code "178") (name "unconnected-(JA-Pad1)") (class "Default")
      (node (ref "JA") (pin "1") (pinfunction "1_1") (pintype "passive"))
    )
    (net (code "179") (name "unconnected-(JA-Pad2)") (class "Default")
      (node (ref "JA") (pin "2") (pinfunction "2_2") (pintype "passive"))
    )
    (net (code "180") (name "unconnected-(JB-Pad1)") (class "Default")
      (node (ref "JB") (pin "1") (pinfunction "1_1") (pintype "passive"))
    )
    (net (code "181") (name "unconnected-(JB-Pad2)") (class "Default")
      (node (ref "JB") (pin "2") (pinfunction "2_2") (pintype "passive"))
    )
    (net (code "182") (name "unconnected-(JE1-Pad3)") (class "Default")
      (node (ref "JE1") (pin "3") (pinfunction "3_3") (pintype "passive"))
    )
    (net (code "183") (name "unconnected-(JE1-Pad5)") (class "Default")
      (node (ref "JE1") (pin "5") (pinfunction "5_5") (pintype "passive"))
    )
    (net (code "184") (name "unconnected-(JE1-Pad6)") (class "Default")
      (node (ref "JE1") (pin "6") (pinfunction "6_6") (pintype "passive"))
    )
    (net (code "185") (name "unconnected-(JP8-Pad5)") (class "Default")
      (node (ref "JP8") (pin "5") (pinfunction "5_5") (pintype "passive"))
    )
    (net (code "186") (name "unconnected-(JP8-Pad6)") (class "Default")
      (node (ref "JP8") (pin "6") (pinfunction "6_6") (pintype "passive"))
    )
    (net (code "187") (name "unconnected-(SPI0-Pad2)") (class "Default")
      (node (ref "SPI0") (pin "2") (pinfunction "2_2") (pintype "passive"))
    )
    (net (code "188") (name "unconnected-(XDHT11-Pad3)") (class "Default")
      (node (ref "XDHT11") (pin "3") (pinfunction "3_3") (pintype "passive"))
    )
  )
)
